# BANK1.net
KiCad netlist of a schematic drawn in Altium Designer
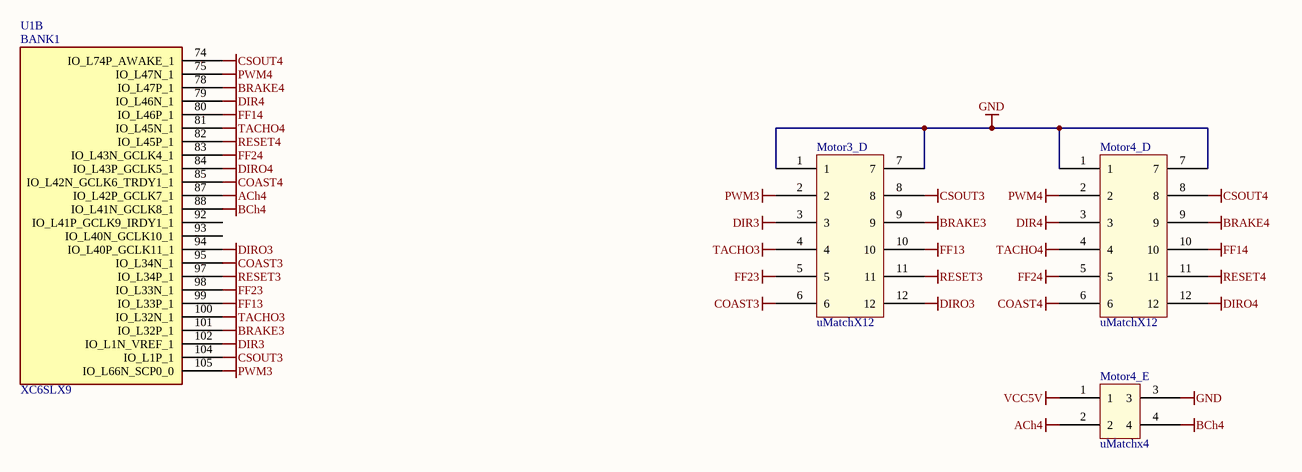
[diagram p0: BANK1.SchDoc]

(export (version "E")
  (design (tool "Eeschema 10.0.6"))
  (components
    (comp (ref "Motor3_D")
      (value "uMatchX12")
      (footprint "uMatchX12")
      (libsource (lib "Mainboard_component_schematics") (part "uMatchX12"))
    )
    (comp (ref "Motor4_D")
      (value "uMatchX12")
      (footprint "uMatchX12")
      (libsource (lib "Mainboard_component_schematics") (part "uMatchX12"))
    )
    (comp (ref "Motor4_E")
      (value "uMatchx4")
      (footprint "Micromatch x4")
      (libsource (lib "Mainboard_component_schematics") (part "uMatchx4"))
    )
    (comp (ref "U1")
      (value "XC6SLX9")
      (footprint "XC6SLX9")
      (description "Imported")
      (libsource (lib "Mainboard_component_schematics") (part "C6SLX9"))
    )
  )
  (nets
    (net (code "1") (name "ACh4") (class "Default")
      (node (ref "Motor4_E") (pin "2") (pinfunction "2_2") (pintype "passive"))
      (node (ref "U1") (pin "87") (pinfunction "IO_L42P_GCLK7_1_87") (pintype "passive"))
    )
    (net (code "2") (name "BCh4") (class "Default")
      (node (ref "Motor4_E") (pin "4") (pinfunction "4_4") (pintype "passive"))
      (node (ref "U1") (pin "88") (pinfunction "IO_L41N_GCLK8_1_88") (pintype "passive"))
    )
    (net (code "3") (name "BRAKE3") (class "Default")
      (node (ref "Motor3_D") (pin "9") (pinfunction "9_9") (pintype "passive"))
      (node (ref "U1") (pin "101") (pinfunction "IO_L32P_1_101") (pintype "passive"))
    )
    (net (code "4") (name "BRAKE4") (class "Default")
      (node (ref "Motor4_D") (pin "9") (pinfunction "9_9") (pintype "passive"))
      (node (ref "U1") (pin "78") (pinfunction "IO_L47P_1_78") (pintype "passive"))
    )
    (net (code "5") (name "COAST3") (class "Default")
      (node (ref "Motor3_D") (pin "6") (pinfunction "6_6") (pintype "passive"))
      (node (ref "U1") (pin "95") (pinfunction "IO_L34N_1_95") (pintype "passive"))
    )
    (net (code "6") (name "COAST4") (class "Default")
      (node (ref "Motor4_D") (pin "6") (pinfunction "6_6") (pintype "passive"))
      (node (ref "U1") (pin "85") (pinfunction "IO_L42N_GCLK6_TRDY1_1_85") (pintype "passive"))
    )
    (net (code "7") (name "CSOUT3") (class "Default")
      (node (ref "Motor3_D") (pin "8") (pinfunction "8_8") (pintype "passive"))
      (node (ref "U1") (pin "104") (pinfunction "IO_L1P_1_104") (pintype "passive"))
    )
    (net (code "8") (name "CSOUT4") (class "Default")
      (node (ref "Motor4_D") (pin "8") (pinfunction "8_8") (pintype "passive"))
      (node (ref "U1") (pin "74") (pinfunction "IO_L74P_AWAKE_1_74") (pintype "passive"))
    )
    (net (code "9") (name "DIR3") (class "Default")
      (node (ref "Motor3_D") (pin "3") (pinfunction "3_3") (pintype "passive"))
      (node (ref "U1") (pin "102") (pinfunction "IO_L1N_VREF_1_102") (pintype "passive"))
    )
    (net (code "10") (name "DIR4") (class "Default")
      (node (ref "Motor4_D") (pin "3") (pinfunction "3_3") (pintype "passive"))
      (node (ref "U1") (pin "79") (pinfunction "IO_L46N_1_79") (pintype "passive"))
    )
    (net (code "11") (name "DIRO3") (class "Default")
      (node (ref "Motor3_D") (pin "12") (pinfunction "12_12") (pintype "passive"))
      (node (ref "U1") (pin "94") (pinfunction "IO_L40P_GCLK11_1_94") (pintype "passive"))
    )
    (net (code "12") (name "DIRO4") (class "Default")
      (node (ref "Motor4_D") (pin "12") (pinfunction "12_12") (pintype "passive"))
      (node (ref "U1") (pin "84") (pinfunction "IO_L43P_GCLK5_1_84") (pintype "passive"))
    )
    (net (code "13") (name "FF13") (class "Default")
      (node (ref "Motor3_D") (pin "10") (pinfunction "10_10") (pintype "passive"))
      (node (ref "U1") (pin "99") (pinfunction "IO_L33P_1_99") (pintype "passive"))
    )
    (net (code "14") (name "FF14") (class "Default")
      (node (ref "Motor4_D") (pin "10") (pinfunction "10_10") (pintype "passive"))
      (node (ref "U1") (pin "80") (pinfunction "IO_L46P_1_80") (pintype "passive"))
    )
    (net (code "15") (name "FF23") (class "Default")
      (node (ref "Motor3_D") (pin "5") (pinfunction "5_5") (pintype "passive"))
      (node (ref "U1") (pin "98") (pinfunction "IO_L33N_1_98") (pintype "passive"))
    )
    (net (code "16") (name "FF24") (class "Default")
      (node (ref "Motor4_D") (pin "5") (pinfunction "5_5") (pintype "passive"))
      (node (ref "U1") (pin "83") (pinfunction "IO_L43N_GCLK4_1_83") (pintype "passive"))
    )
    (net (code "17") (name "GND") (class "Default")
      (node (ref "Motor3_D") (pin "1") (pinfunction "1_1") (pintype "passive"))
      (node (ref "Motor3_D") (pin "7") (pinfunction "7_7") (pintype "passive"))
      (node (ref "Motor4_D") (pin "1") (pinfunction "1_1") (pintype "passive"))
      (node (ref "Motor4_D") (pin "7") (pinfunction "7_7") (pintype "passive"))
      (node (ref "Motor4_E") (pin "3") (pinfunction "3_3") (pintype "passive"))
    )
    (net (code "18") (name "PWM3") (class "Default")
      (node (ref "Motor3_D") (pin "2") (pinfunction "2_2") (pintype "passive"))
      (node (ref "U1") (pin "105") (pinfunction "IO_L66N_SCP0_0_105") (pintype "passive"))
    )
    (net (code "19") (name "PWM4") (class "Default")
      (node (ref "Motor4_D") (pin "2") (pinfunction "2_2") (pintype "passive"))
      (node (ref "U1") (pin "75") (pinfunction "IO_L47N_1_75") (pintype "passive"))
    )
    (net (code "20") (name "RESET3") (class "Default")
      (node (ref "Motor3_D") (pin "11") (pinfunction "11_11") (pintype "passive"))
      (node (ref "U1") (pin "97") (pinfunction "IO_L34P_1_97") (pintype "passive"))
    )
    (net (code "21") (name "RESET4") (class "Default")
      (node (ref "Motor4_D") (pin "11") (pinfunction "11_11") (pintype "passive"))
      (node (ref "U1") (pin "82") (pinfunction "IO_L45P_1_82") (pintype "passive"))
    )
    (net (code "22") (name "TACHO3") (class "Default")
      (node (ref "Motor3_D") (pin "4") (pinfunction "4_4") (pintype "passive"))
      (node (ref "U1") (pin "100") (pinfunction "IO_L32N_1_100") (pintype "passive"))
    )
    (net (code "23") (name "TACHO4") (class "Default")
      (node (ref "Motor4_D") (pin "4") (pinfunction "4_4") (pintype "passive"))
      (node (ref "U1") (pin "81") (pinfunction "IO_L45N_1_81") (pintype "passive"))
    )
    (net (code "24") (name "VCC5V") (class "Default")
      (node (ref "Motor4_E") (pin "1") (pinfunction "1_1") (pintype "passive"))
    )
    (net (code "25") (name "unconnected-(U1B-IO_L40N_GCLK10_1-Pad93)") (class "Default")
      (node (ref "U1") (pin "93") (pinfunction "IO_L40N_GCLK10_1_93") (pintype "passive"))
    )
    (net (code "26") (name "unconnected-(U1B-IO_L41P_GCLK9_IRDY1_1-Pad92)") (class "Default")
      (node (ref "U1") (pin "92") (pinfunction "IO_L41P_GCLK9_IRDY1_1_92") (pintype "passive"))
    )
  )
)
